# SVL-AuxiliaryPower.net
KiCad netlist of a schematic drawn in EAGLE
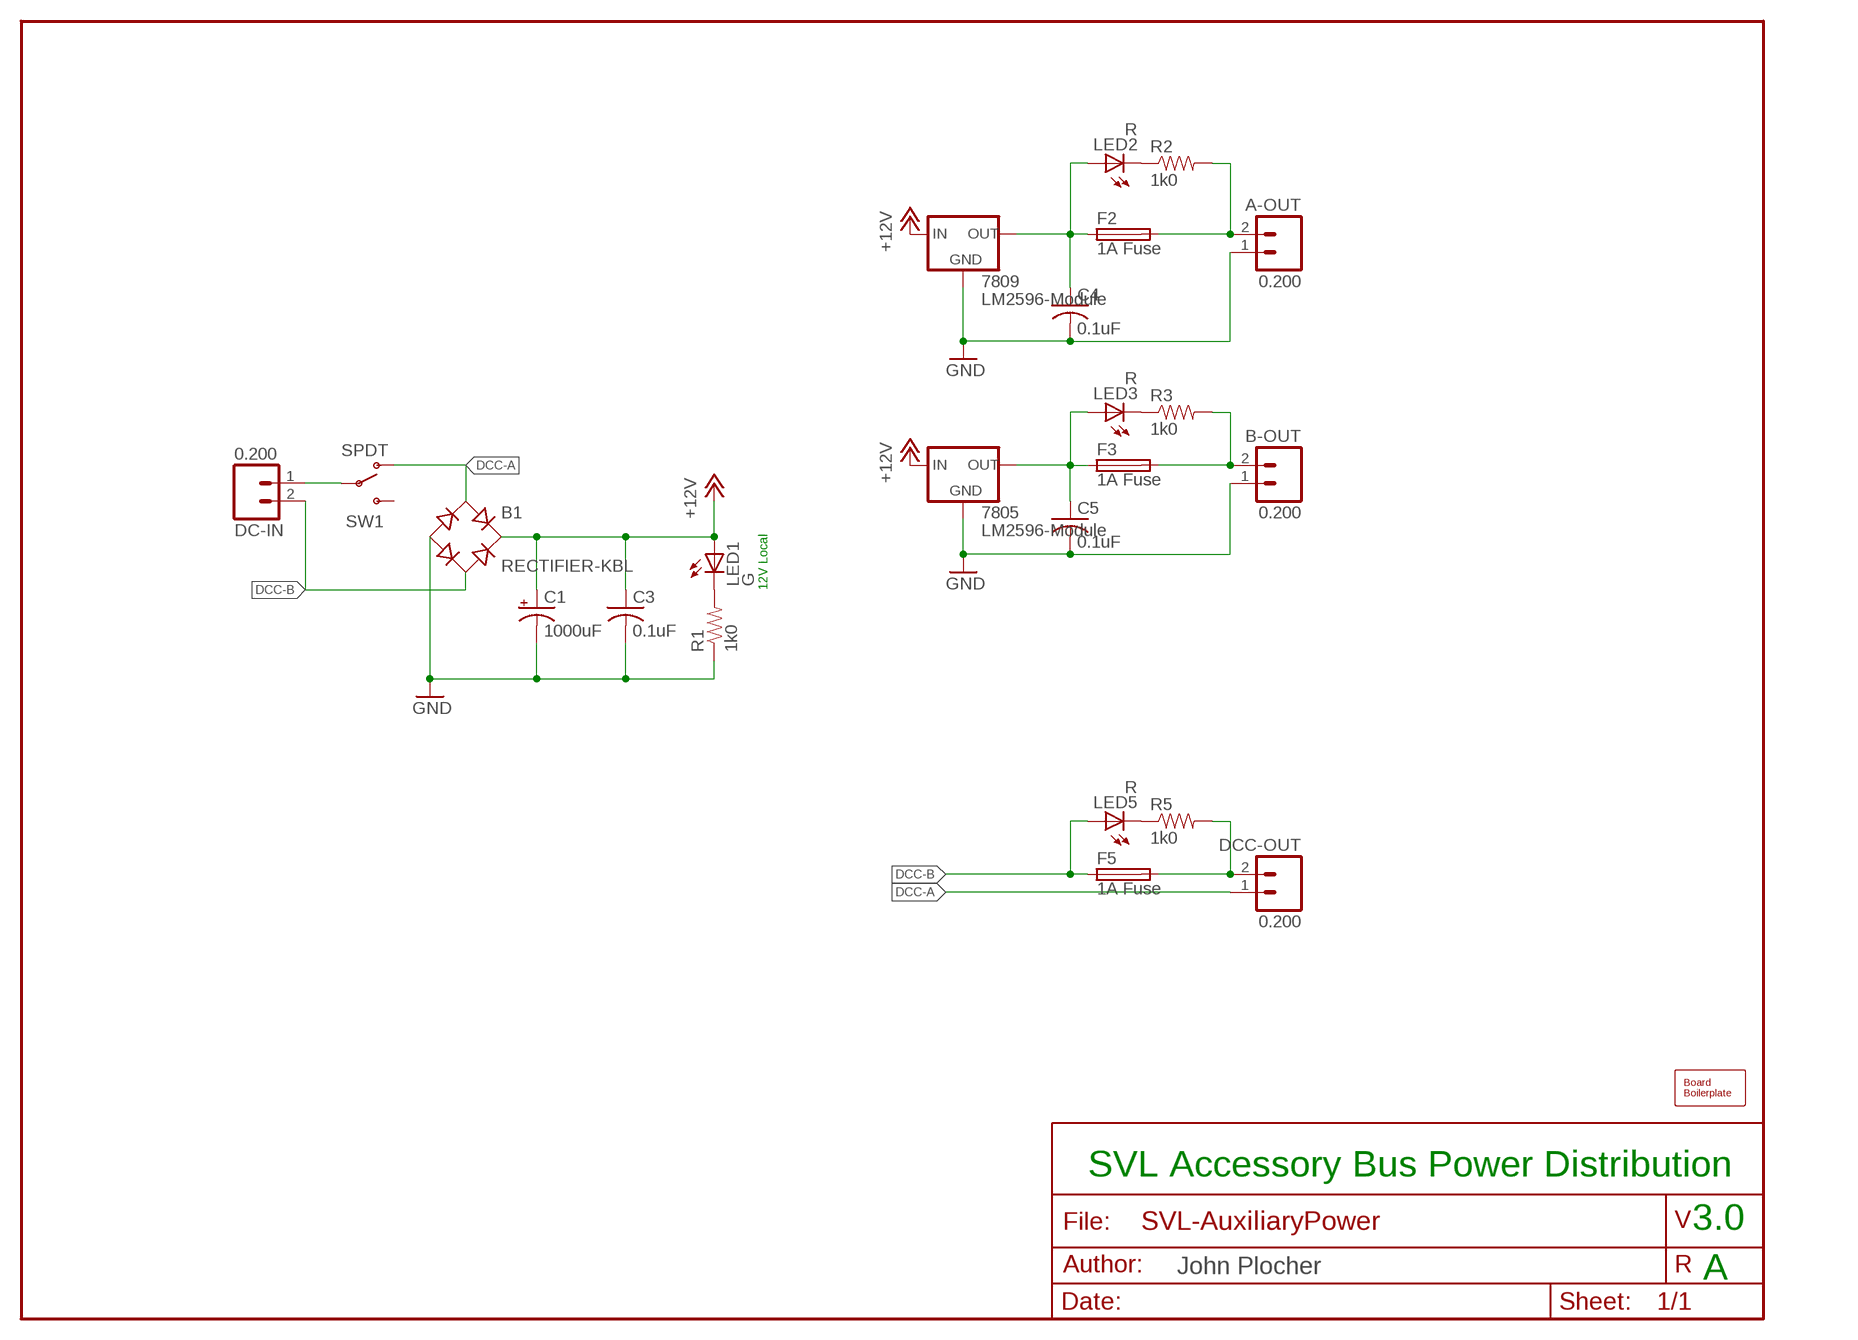
[diagram p0: schematic, sheet 1]

(export (version "E")
  (design (tool "Eeschema 10.0.6"))
  (components
    (comp (ref "7805")
      (value "LM2596-Module")
      (footprint "eagle-import:LM2596-MODULE")
      (libsource (lib "eagle-import") (part "VREG_78XXLM2596"))
    )
    (comp (ref "7809")
      (value "LM2596-Module")
      (footprint "eagle-import:LM2596-MODULE")
      (libsource (lib "eagle-import") (part "VREG_78XXLM2596"))
    )
    (comp (ref "A-OUT")
      (value "0.200")
      (footprint "eagle-import:MSTB2")
      (libsource (lib "eagle-import") (part "CONNECTOR-M02508-LOCK"))
    )
    (comp (ref "B-OUT")
      (value "0.200")
      (footprint "eagle-import:MSTB2")
      (libsource (lib "eagle-import") (part "CONNECTOR-M02508-LOCK"))
    )
    (comp (ref "B1")
      (value "RECTIFIER-KBL")
      (footprint "eagle-import:KBL")
      (libsource (lib "eagle-import") (part "RECTIFIER-KBL"))
    )
    (comp (ref "BOARD1")
      (value "BOARD100X100")
      (footprint "eagle-import:BOARD-SEEED10X10")
      (libsource (lib "eagle-import") (part "BOARD100X100"))
    )
    (comp (ref "C1")
      (value "1000uF")
      (footprint "eagle-import:E5-10.5")
      (libsource (lib "eagle-import") (part "CAP-POLPTH-5MM"))
    )
    (comp (ref "C3")
      (value "0.1uF")
      (footprint "eagle-import:C050-024X044")
      (libsource (lib "eagle-import") (part "CAPPTH1"))
    )
    (comp (ref "C4")
      (value "0.1uF")
      (footprint "eagle-import:C050-024X044")
      (libsource (lib "eagle-import") (part "CAPPTH1"))
    )
    (comp (ref "C5")
      (value "0.1uF")
      (footprint "eagle-import:C050-024X044")
      (libsource (lib "eagle-import") (part "CAPPTH1"))
    )
    (comp (ref "DC-IN")
      (value "0.200")
      (footprint "eagle-import:MSTB2")
      (libsource (lib "eagle-import") (part "CONNECTOR-M02508-LOCK"))
    )
    (comp (ref "DCC-OUT")
      (value "0.200")
      (footprint "eagle-import:MSTB2")
      (libsource (lib "eagle-import") (part "CONNECTOR-M02508-LOCK"))
    )
    (comp (ref "F2")
      (value "1A Fuse")
      (footprint "eagle-import:POLYFUSE")
      (libsource (lib "eagle-import") (part "PICOFUSEPOLY"))
    )
    (comp (ref "F3")
      (value "1A Fuse")
      (footprint "eagle-import:POLYFUSE")
      (libsource (lib "eagle-import") (part "PICOFUSEPOLY"))
    )
    (comp (ref "F5")
      (value "1A Fuse")
      (footprint "eagle-import:POLYFUSE")
      (libsource (lib "eagle-import") (part "PICOFUSEPOLY"))
    )
    (comp (ref "LED1")
      (value "G")
      (footprint "eagle-import:LED5MM")
      (libsource (lib "eagle-import") (part "LEDLED5MM"))
    )
    (comp (ref "LED2")
      (value "R")
      (footprint "eagle-import:LED5MM")
      (libsource (lib "eagle-import") (part "LEDLED5MM"))
    )
    (comp (ref "LED3")
      (value "R")
      (footprint "eagle-import:LED5MM")
      (libsource (lib "eagle-import") (part "LEDLED5MM"))
    )
    (comp (ref "LED5")
      (value "R")
      (footprint "eagle-import:LED5MM")
      (libsource (lib "eagle-import") (part "LEDLED5MM"))
    )
    (comp (ref "R1")
      (value "1k0")
      (footprint "eagle-import:AXIAL-0.4-RES")
      (libsource (lib "eagle-import") (part "RPTH04"))
    )
    (comp (ref "R2")
      (value "1k0")
      (footprint "eagle-import:AXIAL-0.4-RES")
      (libsource (lib "eagle-import") (part "RPTH04"))
    )
    (comp (ref "R3")
      (value "1k0")
      (footprint "eagle-import:AXIAL-0.4-RES")
      (libsource (lib "eagle-import") (part "RPTH04"))
    )
    (comp (ref "R5")
      (value "1k0")
      (footprint "eagle-import:AXIAL-0.4-RES")
      (libsource (lib "eagle-import") (part "RPTH04"))
    )
    (comp (ref "SW1")
      (value "SPDT")
      (footprint "eagle-import:SWITCH-SPDT-508")
      (libsource (lib "eagle-import") (part "SWITCH-SPSTPTH-508"))
    )
  )
  (nets
    (net (code "1") (name "+12V") (class "Default")
      (node (ref "7805") (pin "IN+@1") (pinfunction "IN_IN+@1") (pintype "input"))
      (node (ref "7805") (pin "IN+@2") (pinfunction "IN_IN+@2") (pintype "input"))
      (node (ref "7809") (pin "IN+@1") (pinfunction "IN_IN+@1") (pintype "input"))
      (node (ref "7809") (pin "IN+@2") (pinfunction "IN_IN+@2") (pintype "input"))
      (node (ref "B1") (pin "+") (pinfunction "+_+") (pintype "passive"))
      (node (ref "C1") (pin "+") (pinfunction "+_+") (pintype "passive"))
      (node (ref "C3") (pin "1") (pinfunction "1_1") (pintype "passive"))
      (node (ref "LED1") (pin "A") (pinfunction "A_A") (pintype "passive"))
    )
    (net (code "2") (name "DCC-A") (class "Default")
      (node (ref "B1") (pin "AC1") (pinfunction "AC1_AC1") (pintype "passive"))
      (node (ref "DCC-OUT") (pin "1") (pinfunction "1_1") (pintype "passive"))
      (node (ref "SW1") (pin "1") (pinfunction "O_1") (pintype "passive"))
    )
    (net (code "3") (name "DCC-B") (class "Default")
      (node (ref "B1") (pin "AC2") (pinfunction "AC2_AC2") (pintype "passive"))
      (node (ref "DC-IN") (pin "2") (pinfunction "2_2") (pintype "passive"))
      (node (ref "F5") (pin "1") (pinfunction "1_1") (pintype "passive"))
      (node (ref "LED5") (pin "A") (pinfunction "A_A") (pintype "passive"))
    )
    (net (code "4") (name "GND") (class "Default")
      (node (ref "7805") (pin "GND@1") (pinfunction "GND_GND@1") (pintype "input"))
      (node (ref "7805") (pin "GND@2") (pinfunction "GND_GND@2") (pintype "input"))
      (node (ref "7805") (pin "GND@3") (pinfunction "GND_GND@3") (pintype "input"))
      (node (ref "7805") (pin "GND@4") (pinfunction "GND_GND@4") (pintype "input"))
      (node (ref "7809") (pin "GND@1") (pinfunction "GND_GND@1") (pintype "input"))
      (node (ref "7809") (pin "GND@2") (pinfunction "GND_GND@2") (pintype "input"))
      (node (ref "7809") (pin "GND@3") (pinfunction "GND_GND@3") (pintype "input"))
      (node (ref "7809") (pin "GND@4") (pinfunction "GND_GND@4") (pintype "input"))
      (node (ref "A-OUT") (pin "1") (pinfunction "1_1") (pintype "passive"))
      (node (ref "B-OUT") (pin "1") (pinfunction "1_1") (pintype "passive"))
      (node (ref "B1") (pin "-") (pinfunction "-_-") (pintype "passive"))
      (node (ref "C1") (pin "-") (pinfunction "-_-") (pintype "passive"))
      (node (ref "C3") (pin "2") (pinfunction "2_2") (pintype "passive"))
      (node (ref "C4") (pin "2") (pinfunction "2_2") (pintype "passive"))
      (node (ref "C5") (pin "2") (pinfunction "2_2") (pintype "passive"))
      (node (ref "R1") (pin "P$1") (pinfunction "1_P$1") (pintype "passive"))
    )
    (net (code "5") (name "Net-(7805-OUT-PadOUT+@1)") (class "Default")
      (node (ref "7805") (pin "OUT+@1") (pinfunction "OUT_OUT+@1") (pintype "output"))
      (node (ref "7805") (pin "OUT+@2") (pinfunction "OUT_OUT+@2") (pintype "output"))
      (node (ref "C5") (pin "1") (pinfunction "1_1") (pintype "passive"))
      (node (ref "F3") (pin "1") (pinfunction "1_1") (pintype "passive"))
      (node (ref "LED3") (pin "A") (pinfunction "A_A") (pintype "passive"))
    )
    (net (code "6") (name "Net-(7809-OUT-PadOUT+@1)") (class "Default")
      (node (ref "7809") (pin "OUT+@1") (pinfunction "OUT_OUT+@1") (pintype "output"))
      (node (ref "7809") (pin "OUT+@2") (pinfunction "OUT_OUT+@2") (pintype "output"))
      (node (ref "C4") (pin "1") (pinfunction "1_1") (pintype "passive"))
      (node (ref "F2") (pin "1") (pinfunction "1_1") (pintype "passive"))
      (node (ref "LED2") (pin "A") (pinfunction "A_A") (pintype "passive"))
    )
    (net (code "7") (name "Net-(LED1-C)") (class "Default")
      (node (ref "LED1") (pin "K") (pinfunction "C_K") (pintype "passive"))
      (node (ref "R1") (pin "P$2") (pinfunction "2_P$2") (pintype "passive"))
    )
    (net (code "8") (name "Net-(LED2-C)") (class "Default")
      (node (ref "LED2") (pin "K") (pinfunction "C_K") (pintype "passive"))
      (node (ref "R2") (pin "P$1") (pinfunction "1_P$1") (pintype "passive"))
    )
    (net (code "9") (name "Net-(LED3-C)") (class "Default")
      (node (ref "LED3") (pin "K") (pinfunction "C_K") (pintype "passive"))
      (node (ref "R3") (pin "P$1") (pinfunction "1_P$1") (pintype "passive"))
    )
    (net (code "10") (name "Net-(LED5-C)") (class "Default")
      (node (ref "LED5") (pin "K") (pinfunction "C_K") (pintype "passive"))
      (node (ref "R5") (pin "P$1") (pinfunction "1_P$1") (pintype "passive"))
    )
    (net (code "11") (name "Net-(R2-2)") (class "Default")
      (node (ref "A-OUT") (pin "2") (pinfunction "2_2") (pintype "passive"))
      (node (ref "F2") (pin "2") (pinfunction "2_2") (pintype "passive"))
      (node (ref "R2") (pin "P$2") (pinfunction "2_P$2") (pintype "passive"))
    )
    (net (code "12") (name "Net-(R3-2)") (class "Default")
      (node (ref "B-OUT") (pin "2") (pinfunction "2_2") (pintype "passive"))
      (node (ref "F3") (pin "2") (pinfunction "2_2") (pintype "passive"))
      (node (ref "R3") (pin "P$2") (pinfunction "2_P$2") (pintype "passive"))
    )
    (net (code "13") (name "Net-(R5-2)") (class "Default")
      (node (ref "DCC-OUT") (pin "2") (pinfunction "2_2") (pintype "passive"))
      (node (ref "F5") (pin "2") (pinfunction "2_2") (pintype "passive"))
      (node (ref "R5") (pin "P$2") (pinfunction "2_P$2") (pintype "passive"))
    )
    (net (code "14") (name "Net-(SW1-P)") (class "Default")
      (node (ref "DC-IN") (pin "1") (pinfunction "1_1") (pintype "passive"))
      (node (ref "SW1") (pin "2") (pinfunction "P_2") (pintype "passive"))
    )
    (net (code "15") (name "unconnected-(SW1-S-Pad3)") (class "Default")
      (node (ref "SW1") (pin "3") (pinfunction "S_3") (pintype "passive"))
    )
  )
)
